# XbeeBed.net
KiCad netlist of a schematic drawn in Altium Designer
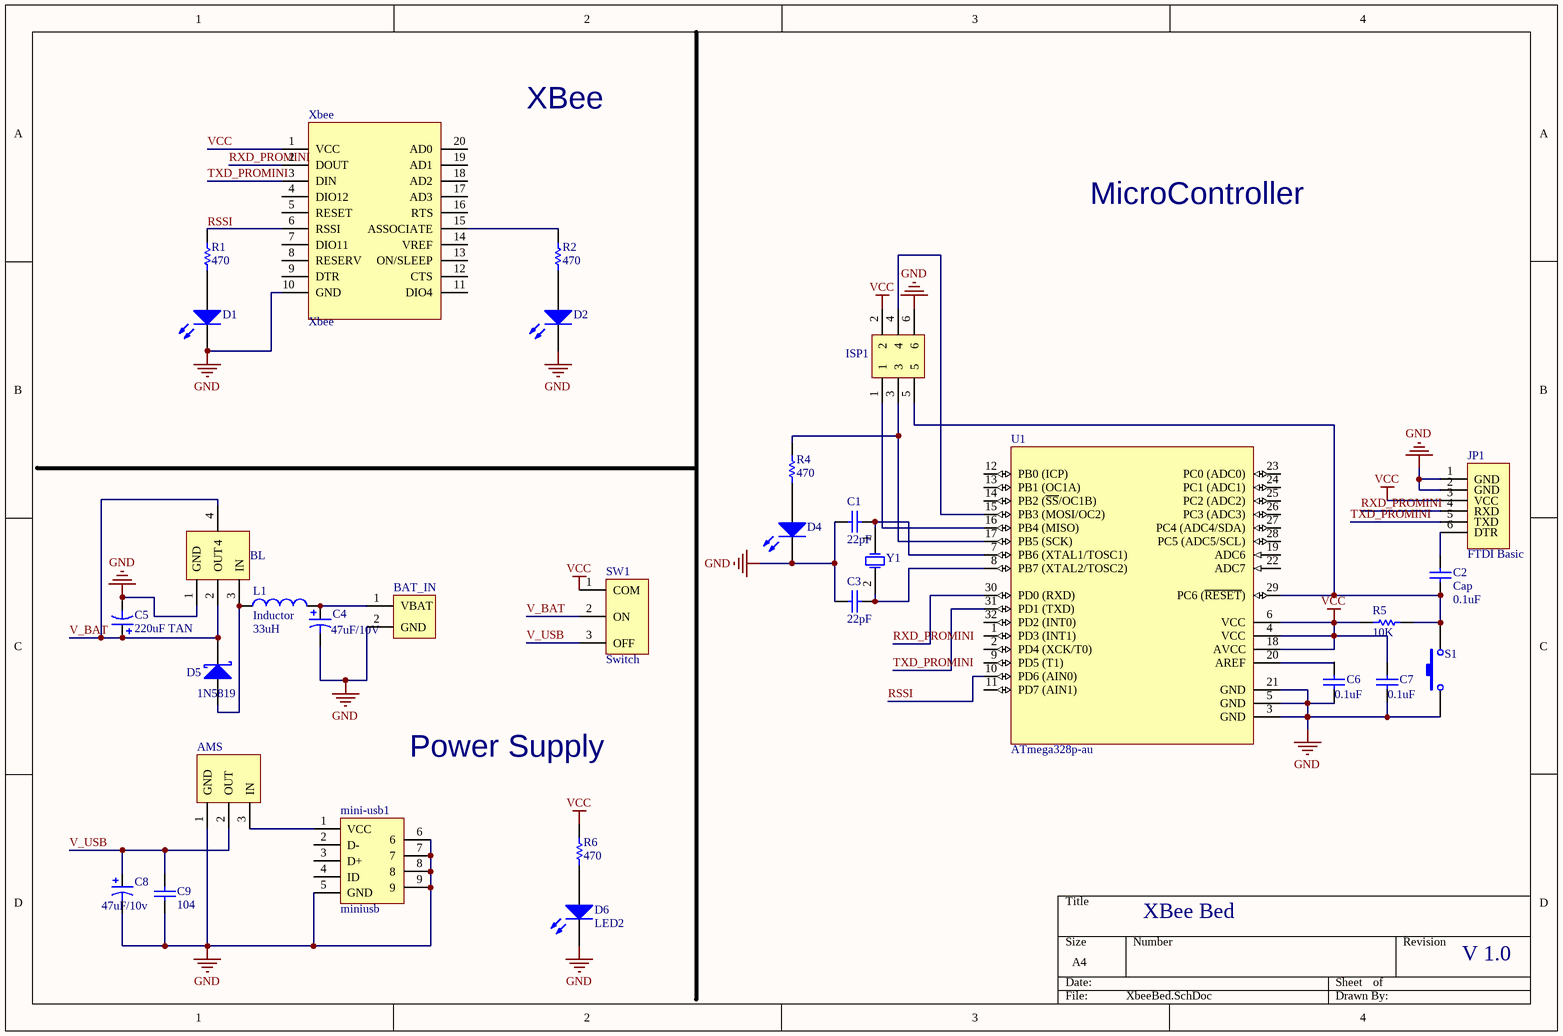
[diagram p0: XbeeBed.SchDoc]

(export (version "E")
  (design (tool "Eeschema 10.0.6"))
  (components
    (comp (ref "AMS")
      (value "AMS1117-3.3CD")
      (footprint "SOT223")
      (libsource (lib "*") (part "AMS1117-3.3CD"))
    )
    (comp (ref "BAT_IN") (value "BATTERY INPUT") (footprint "vbat_in") (libsource (lib "*") (part "BAT_IN")))
    (comp (ref "BL") (value "BL8530-331SM") (footprint "SOT89") (libsource (lib "*") (part "BL8530-331SM")))
    (comp (ref "C1")
      (value "22pF")
      (footprint "0805")
      (description "Capacitor")
      (fields (field (name "Comment") "Cap") (field (name "PUBLISHER") "Altium Limited"))
      (libsource (lib "Miscellaneous Devices") (part "Cap"))
    )
    (comp (ref "C2")
      (value "Cap")
      (footprint "0805")
      (description "Capacitor")
      (fields (field (name "ALTIUM_VALUE") "0.1uF") (field (name "PUBLISHER") "Altium Limited"))
      (libsource (lib "Miscellaneous Devices") (part "Cap"))
    )
    (comp (ref "C3")
      (value "22pF")
      (footprint "0805")
      (description "Capacitor")
      (fields (field (name "Comment") "Cap") (field (name "PUBLISHER") "Altium Limited"))
      (libsource (lib "Miscellaneous Devices") (part "Cap"))
    )
    (comp (ref "C4")
      (value "47uF/10V")
      (footprint "tan-c type")
      (description "Polarized Capacitor (Surface Mount)")
      (fields (field (name "Comment") "Cap Pol3") (field (name "PUBLISHER") "Altium Limited"))
      (libsource (lib "Miscellaneous Devices") (part "Cap Pol3"))
    )
    (comp (ref "C5")
      (value "220uF TAN")
      (footprint "tan-d type")
      (description "Polarized Capacitor (Surface Mount)")
      (fields (field (name "Comment") "Cap Pol3") (field (name "PUBLISHER") "Altium Limited"))
      (libsource (lib "") (part "Cap Pol3_1"))
    )
    (comp (ref "C6")
      (value "0.1uF")
      (footprint "0805")
      (description "Capacitor")
      (fields (field (name "Comment") "Cap") (field (name "PUBLISHER") "Altium Limited"))
      (libsource (lib "Miscellaneous Devices") (part "Cap"))
    )
    (comp (ref "C7")
      (value "0.1uF")
      (footprint "0805")
      (description "Capacitor")
      (fields (field (name "Comment") "Cap") (field (name "PUBLISHER") "Altium Limited"))
      (libsource (lib "Miscellaneous Devices") (part "Cap"))
    )
    (comp (ref "C8")
      (value "47uF/10v")
      (footprint "tan-c type")
      (description "Polarized Capacitor (Surface Mount)")
      (fields (field (name "Comment") "Cap Pol3") (field (name "PUBLISHER") "Altium Limited"))
      (libsource (lib "Miscellaneous Devices") (part "Cap Pol3"))
    )
    (comp (ref "C9")
      (value "104")
      (footprint "0805")
      (description "Capacitor")
      (fields (field (name "Comment") "Cap") (field (name "PUBLISHER") "Altium Limited"))
      (libsource (lib "Miscellaneous Devices") (part "Cap"))
    )
    (comp (ref "D1")
      (value "LED2")
      (footprint "0805")
      (description "Typical RED, GREEN, YELLOW, AMBER GaAs LED")
      (fields (field (name "PUBLISHER") "Altium Limited"))
      (libsource (lib "Miscellaneous Devices") (part "LED2"))
    )
    (comp (ref "D2")
      (value "LED2")
      (footprint "0805")
      (description "Typical RED, GREEN, YELLOW, AMBER GaAs LED")
      (fields (field (name "PUBLISHER") "Altium Limited"))
      (libsource (lib "Miscellaneous Devices") (part "LED2"))
    )
    (comp (ref "D4")
      (value "LED2")
      (footprint "0805")
      (description "Typical RED, GREEN, YELLOW, AMBER GaAs LED")
      (fields (field (name "PUBLISHER") "Altium Limited"))
      (libsource (lib "Miscellaneous Devices") (part "LED2"))
    )
    (comp (ref "D5")
      (value "1N5819")
      (footprint "1n5819")
      (description "Schottky Rectifier")
      (fields (field (name "PUBLISHER") "Altium Limited"))
      (libsource (lib "Miscellaneous Devices") (part "Diode 11DQ03"))
    )
    (comp (ref "D6")
      (value "LED2")
      (footprint "0805")
      (description "Typical RED, GREEN, YELLOW, AMBER GaAs LED")
      (fields (field (name "PUBLISHER") "Altium Limited"))
      (libsource (lib "Miscellaneous Devices") (part "LED2"))
    )
    (comp (ref "ISP1") (value "ISP INTERFACE") (footprint "icsp") (libsource (lib "*") (part "ISP")))
    (comp (ref "JP1") (value "FTDI Basic") (footprint "ftdi-basic") (libsource (lib "*") (part "FTDI Basic")))
    (comp (ref "L1")
      (value "Inductor")
      (footprint "33uh-cd43")
      (fields (field (name "ALTIUM_VALUE") "33uH") (field (name "PUBLISHER") "Altium Limited"))
      (libsource (lib "Miscellaneous Devices") (part "Inductor"))
    )
    (comp (ref "mini-usb1") (value "miniusb") (footprint "mini USB") (libsource (lib "*") (part "Mini-Usb")))
    (comp (ref "R1")
      (value "470")
      (footprint "0805")
      (description "Resistor")
      (fields (field (name "Comment") "Res1") (field (name "PUBLISHER") "Altium Limited"))
      (libsource (lib "Miscellaneous Devices") (part "Res1"))
    )
    (comp (ref "R2")
      (value "470")
      (footprint "0805")
      (description "Resistor")
      (fields (field (name "Comment") "Res1") (field (name "PUBLISHER") "Altium Limited"))
      (libsource (lib "Miscellaneous Devices") (part "Res1"))
    )
    (comp (ref "R4")
      (value "470")
      (footprint "0805")
      (description "Resistor")
      (fields (field (name "Comment") "Res1") (field (name "PUBLISHER") "Altium Limited"))
      (libsource (lib "Miscellaneous Devices") (part "Res1"))
    )
    (comp (ref "R5")
      (value "10K")
      (footprint "0805")
      (description "Resistor")
      (fields (field (name "Comment") "Res1") (field (name "PUBLISHER") "Altium Limited"))
      (libsource (lib "Miscellaneous Devices") (part "Res1"))
    )
    (comp (ref "R6")
      (value "470")
      (footprint "0805")
      (description "Resistor")
      (fields (field (name "Comment") "Res1") (field (name "PUBLISHER") "Altium Limited"))
      (libsource (lib "Miscellaneous Devices") (part "Res1"))
    )
    (comp (ref "S1")
      (value "SW-PB")
      (footprint "sw-pb")
      (description "Switch")
      (fields (field (name "PUBLISHER") "Altium Limited"))
      (libsource (lib "Miscellaneous Devices") (part "SW-PB"))
    )
    (comp (ref "SW1") (value "Switch") (footprint "switch") (libsource (lib "*") (part "SW")))
    (comp (ref "U1")
      (value "ATmega328p-au")
      (footprint "atmega328")
      (description "8-Bit AVR Microcontroller with 8K Bytes of In-System Programmable Flash Memory")
      (fields (field (name "PUBLISHER") "Altium Limited"))
      (libsource (lib "Atmel Microcontroller 8-Bit AVR") (part "ATmega8-16AC"))
    )
    (comp (ref "Xbee") (value "Xbee") (footprint "xbee") (libsource (lib "*") (part "Xbee")))
    (comp (ref "Y1")
      (value "XTAL")
      (footprint "8MHz")
      (description "Crystal Oscillator")
      (fields (field (name "PUBLISHER") "Altium Limited"))
      (libsource (lib "Miscellaneous Devices") (part "XTAL"))
    )
  )
  (nets
    (net (code "1") (name "/RSSI") (class "Default")
      (node (ref "R1") (pin "1") (pinfunction "1_1") (pintype "passive"))
      (node (ref "U1") (pin "10") (pinfunction "PD6_(AIN0)_10") (pintype "bidirectional"))
      (node (ref "Xbee") (pin "6") (pinfunction "RSSI_6") (pintype "passive"))
    )
    (net (code "2") (name "/RXD_PROMINI") (class "Default")
      (node (ref "JP1") (pin "4") (pinfunction "RXD_4") (pintype "passive"))
      (node (ref "U1") (pin "30") (pinfunction "PD0_(RXD)_30") (pintype "bidirectional"))
      (node (ref "Xbee") (pin "2") (pinfunction "DOUT_2") (pintype "passive"))
    )
    (net (code "3") (name "/TXD_PROMINI") (class "Default")
      (node (ref "JP1") (pin "5") (pinfunction "TXD_5") (pintype "passive"))
      (node (ref "U1") (pin "31") (pinfunction "PD1_(TXD)_31") (pintype "bidirectional"))
      (node (ref "Xbee") (pin "3") (pinfunction "DIN_3") (pintype "passive"))
    )
    (net (code "4") (name "/V_BAT") (class "Default")
      (node (ref "BL") (pin "2") (pinfunction "OUT_2") (pintype "passive"))
      (node (ref "BL") (pin "4") (pinfunction "4_4") (pintype "passive"))
      (node (ref "C5") (pin "1") (pinfunction "1_1") (pintype "passive"))
      (node (ref "D5") (pin "2") (pinfunction "K_2") (pintype "passive"))
      (node (ref "SW1") (pin "2") (pinfunction "ON_2") (pintype "passive"))
    )
    (net (code "5") (name "/V_USB") (class "Default")
      (node (ref "AMS") (pin "2") (pinfunction "OUT_2") (pintype "passive"))
      (node (ref "C8") (pin "1") (pinfunction "1_1") (pintype "passive"))
      (node (ref "C9") (pin "1") (pinfunction "1_1") (pintype "passive"))
      (node (ref "SW1") (pin "3") (pinfunction "OFF_3") (pintype "passive"))
    )
    (net (code "6") (name "GND") (class "Default")
      (node (ref "AMS") (pin "1") (pinfunction "GND_1") (pintype "passive"))
      (node (ref "BAT_IN") (pin "2") (pinfunction "GND_2") (pintype "passive"))
      (node (ref "BL") (pin "1") (pinfunction "GND_1") (pintype "passive"))
      (node (ref "C1") (pin "2") (pinfunction "2_2") (pintype "passive"))
      (node (ref "C3") (pin "2") (pinfunction "2_2") (pintype "passive"))
      (node (ref "C4") (pin "2") (pinfunction "2_2") (pintype "passive"))
      (node (ref "C5") (pin "2") (pinfunction "2_2") (pintype "passive"))
      (node (ref "C6") (pin "1") (pinfunction "1_1") (pintype "passive"))
      (node (ref "C7") (pin "1") (pinfunction "1_1") (pintype "passive"))
      (node (ref "C8") (pin "2") (pinfunction "2_2") (pintype "passive"))
      (node (ref "C9") (pin "2") (pinfunction "2_2") (pintype "passive"))
      (node (ref "D1") (pin "2") (pinfunction "K_2") (pintype "passive"))
      (node (ref "D2") (pin "2") (pinfunction "K_2") (pintype "passive"))
      (node (ref "D4") (pin "2") (pinfunction "K_2") (pintype "passive"))
      (node (ref "D6") (pin "2") (pinfunction "K_2") (pintype "passive"))
      (node (ref "ISP1") (pin "6") (pinfunction "6_6") (pintype "passive"))
      (node (ref "JP1") (pin "1") (pinfunction "GND_1") (pintype "passive"))
      (node (ref "JP1") (pin "2") (pinfunction "GND_2") (pintype "passive"))
      (node (ref "S1") (pin "1") (pinfunction "1_1") (pintype "passive"))
      (node (ref "U1") (pin "21") (pinfunction "GND_21") (pintype "power_in"))
      (node (ref "U1") (pin "3") (pinfunction "GND_3") (pintype "power_in"))
      (node (ref "U1") (pin "5") (pinfunction "GND_5") (pintype "power_in"))
      (node (ref "Xbee") (pin "10") (pinfunction "GND_10") (pintype "passive"))
      (node (ref "mini-usb1") (pin "5") (pinfunction "GND_5") (pintype "passive"))
      (node (ref "mini-usb1") (pin "6") (pinfunction "6_6") (pintype "passive"))
      (node (ref "mini-usb1") (pin "7") (pinfunction "7_7") (pintype "passive"))
      (node (ref "mini-usb1") (pin "8") (pinfunction "8_8") (pintype "passive"))
      (node (ref "mini-usb1") (pin "9") (pinfunction "9_9") (pintype "passive"))
    )
    (net (code "7") (name "Net-(AMS-IN)") (class "Default")
      (node (ref "AMS") (pin "3") (pinfunction "IN_3") (pintype "passive"))
      (node (ref "mini-usb1") (pin "1") (pinfunction "VCC_1") (pintype "passive"))
    )
    (net (code "8") (name "Net-(BAT_IN-VBAT)") (class "Default")
      (node (ref "BAT_IN") (pin "1") (pinfunction "VBAT_1") (pintype "passive"))
      (node (ref "C4") (pin "1") (pinfunction "1_1") (pintype "passive"))
      (node (ref "L1") (pin "2") (pinfunction "2_2") (pintype "passive"))
    )
    (net (code "9") (name "Net-(BL-IN)") (class "Default")
      (node (ref "BL") (pin "3") (pinfunction "IN_3") (pintype "passive"))
      (node (ref "D5") (pin "1") (pinfunction "A_1") (pintype "passive"))
      (node (ref "L1") (pin "1") (pinfunction "1_1") (pintype "passive"))
    )
    (net (code "10") (name "Net-(D1-A)") (class "Default")
      (node (ref "D1") (pin "1") (pinfunction "A_1") (pintype "passive"))
      (node (ref "R1") (pin "2") (pinfunction "2_2") (pintype "passive"))
    )
    (net (code "11") (name "Net-(D2-A)") (class "Default")
      (node (ref "D2") (pin "1") (pinfunction "A_1") (pintype "passive"))
      (node (ref "R2") (pin "2") (pinfunction "2_2") (pintype "passive"))
    )
    (net (code "12") (name "Net-(D4-A)") (class "Default")
      (node (ref "D4") (pin "1") (pinfunction "A_1") (pintype "passive"))
      (node (ref "R4") (pin "2") (pinfunction "2_2") (pintype "passive"))
    )
    (net (code "13") (name "Net-(D6-A)") (class "Default")
      (node (ref "D6") (pin "1") (pinfunction "A_1") (pintype "passive"))
      (node (ref "R6") (pin "2") (pinfunction "2_2") (pintype "passive"))
    )
    (net (code "14") (name "Net-(JP1-DTR)") (class "Default")
      (node (ref "C2") (pin "2") (pinfunction "2_2") (pintype "passive"))
      (node (ref "JP1") (pin "6") (pinfunction "DTR_6") (pintype "passive"))
    )
    (net (code "15") (name "Net-(U1-AREF)") (class "Default")
      (node (ref "C6") (pin "2") (pinfunction "2_2") (pintype "passive"))
      (node (ref "U1") (pin "20") (pinfunction "AREF_20") (pintype "passive"))
    )
    (net (code "16") (name "Net-(U1-PB3_(MOSI{slash}OC2))") (class "Default")
      (node (ref "ISP1") (pin "4") (pinfunction "4_4") (pintype "passive"))
      (node (ref "U1") (pin "15") (pinfunction "PB3_(MOSI/OC2)_15") (pintype "bidirectional"))
    )
    (net (code "17") (name "Net-(U1-PB4_(MISO))") (class "Default")
      (node (ref "ISP1") (pin "1") (pinfunction "1_1") (pintype "passive"))
      (node (ref "U1") (pin "16") (pinfunction "PB4_(MISO)_16") (pintype "bidirectional"))
    )
    (net (code "18") (name "Net-(U1-PB5_(SCK))") (class "Default")
      (node (ref "ISP1") (pin "3") (pinfunction "3_3") (pintype "passive"))
      (node (ref "R4") (pin "1") (pinfunction "1_1") (pintype "passive"))
      (node (ref "U1") (pin "17") (pinfunction "PB5_(SCK)_17") (pintype "bidirectional"))
    )
    (net (code "19") (name "Net-(U1-PB6_(XTAL1{slash}TOSC1))") (class "Default")
      (node (ref "C1") (pin "1") (pinfunction "1_1") (pintype "passive"))
      (node (ref "U1") (pin "7") (pinfunction "PB6_(XTAL1/TOSC1)_7") (pintype "bidirectional"))
      (node (ref "Y1") (pin "1") (pinfunction "OSC1_1") (pintype "passive"))
    )
    (net (code "20") (name "Net-(U1-PB7_(XTAL2{slash}TOSC2))") (class "Default")
      (node (ref "C3") (pin "1") (pinfunction "1_1") (pintype "passive"))
      (node (ref "U1") (pin "8") (pinfunction "PB7_(XTAL2/TOSC2)_8") (pintype "bidirectional"))
      (node (ref "Y1") (pin "2") (pinfunction "OSC2_2") (pintype "passive"))
    )
    (net (code "21") (name "Net-(U1-PC6_(~{RESET}))") (class "Default")
      (node (ref "C2") (pin "1") (pinfunction "1_1") (pintype "passive"))
      (node (ref "ISP1") (pin "5") (pinfunction "5_5") (pintype "passive"))
      (node (ref "R5") (pin "1") (pinfunction "1_1") (pintype "passive"))
      (node (ref "S1") (pin "2") (pinfunction "2_2") (pintype "passive"))
      (node (ref "U1") (pin "29") (pinfunction "PC6_(~{RESET})_29") (pintype "bidirectional"))
    )
    (net (code "22") (name "Net-(Xbee-ASSOCIATE)") (class "Default")
      (node (ref "R2") (pin "1") (pinfunction "1_1") (pintype "passive"))
      (node (ref "Xbee") (pin "15") (pinfunction "ASSOCIATE_15") (pintype "passive"))
    )
    (net (code "23") (name "VCC") (class "Default")
      (node (ref "C7") (pin "2") (pinfunction "2_2") (pintype "passive"))
      (node (ref "ISP1") (pin "2") (pinfunction "2_2") (pintype "passive"))
      (node (ref "JP1") (pin "3") (pinfunction "VCC_3") (pintype "passive"))
      (node (ref "R5") (pin "2") (pinfunction "2_2") (pintype "passive"))
      (node (ref "R6") (pin "1") (pinfunction "1_1") (pintype "passive"))
      (node (ref "SW1") (pin "1") (pinfunction "COM_1") (pintype "passive"))
      (node (ref "U1") (pin "18") (pinfunction "AVCC_18") (pintype "power_in"))
      (node (ref "U1") (pin "4") (pinfunction "VCC_4") (pintype "power_in"))
      (node (ref "U1") (pin "6") (pinfunction "VCC_6") (pintype "power_in"))
      (node (ref "Xbee") (pin "1") (pinfunction "VCC_1") (pintype "passive"))
    )
    (net (code "24") (name "unconnected-(U1-ADC6-Pad19)") (class "Default")
      (node (ref "U1") (pin "19") (pinfunction "ADC6_19") (pintype "input"))
    )
    (net (code "25") (name "unconnected-(U1-ADC7-Pad22)") (class "Default")
      (node (ref "U1") (pin "22") (pinfunction "ADC7_22") (pintype "input"))
    )
    (net (code "26") (name "unconnected-(U1-PB0_(ICP)-Pad12)") (class "Default")
      (node (ref "U1") (pin "12") (pinfunction "PB0_(ICP)_12") (pintype "bidirectional"))
    )
    (net (code "27") (name "unconnected-(U1-PB1_(OC1A)-Pad13)") (class "Default")
      (node (ref "U1") (pin "13") (pinfunction "PB1_(OC1A)_13") (pintype "bidirectional"))
    )
    (net (code "28") (name "unconnected-(U1-PB2_(~{SS}{slash}OC1B)-Pad14)") (class "Default")
      (node (ref "U1") (pin "14") (pinfunction "PB2_(~{SS}/OC1B)_14") (pintype "bidirectional"))
    )
    (net (code "29") (name "unconnected-(U1-PC0_(ADC0)-Pad23)") (class "Default")
      (node (ref "U1") (pin "23") (pinfunction "PC0_(ADC0)_23") (pintype "bidirectional"))
    )
    (net (code "30") (name "unconnected-(U1-PC1_(ADC1)-Pad24)") (class "Default")
      (node (ref "U1") (pin "24") (pinfunction "PC1_(ADC1)_24") (pintype "bidirectional"))
    )
    (net (code "31") (name "unconnected-(U1-PC2_(ADC2)-Pad25)") (class "Default")
      (node (ref "U1") (pin "25") (pinfunction "PC2_(ADC2)_25") (pintype "bidirectional"))
    )
    (net (code "32") (name "unconnected-(U1-PC3_(ADC3)-Pad26)") (class "Default")
      (node (ref "U1") (pin "26") (pinfunction "PC3_(ADC3)_26") (pintype "bidirectional"))
    )
    (net (code "33") (name "unconnected-(U1-PC4_(ADC4{slash}SDA)-Pad27)") (class "Default")
      (node (ref "U1") (pin "27") (pinfunction "PC4_(ADC4/SDA)_27") (pintype "bidirectional"))
    )
    (net (code "34") (name "unconnected-(U1-PC5_(ADC5{slash}SCL)-Pad28)") (class "Default")
      (node (ref "U1") (pin "28") (pinfunction "PC5_(ADC5/SCL)_28") (pintype "bidirectional"))
    )
    (net (code "35") (name "unconnected-(U1-PD2_(INT0)-Pad32)") (class "Default")
      (node (ref "U1") (pin "32") (pinfunction "PD2_(INT0)_32") (pintype "bidirectional"))
    )
    (net (code "36") (name "unconnected-(U1-PD3_(INT1)-Pad1)") (class "Default")
      (node (ref "U1") (pin "1") (pinfunction "PD3_(INT1)_1") (pintype "bidirectional"))
    )
    (net (code "37") (name "unconnected-(U1-PD4_(XCK{slash}T0)-Pad2)") (class "Default")
      (node (ref "U1") (pin "2") (pinfunction "PD4_(XCK/T0)_2") (pintype "bidirectional"))
    )
    (net (code "38") (name "unconnected-(U1-PD5_(T1)-Pad9)") (class "Default")
      (node (ref "U1") (pin "9") (pinfunction "PD5_(T1)_9") (pintype "bidirectional"))
    )
    (net (code "39") (name "unconnected-(U1-PD7_(AIN1)-Pad11)") (class "Default")
      (node (ref "U1") (pin "11") (pinfunction "PD7_(AIN1)_11") (pintype "bidirectional"))
    )
    (net (code "40") (name "unconnected-(Xbee-AD0-Pad20)") (class "Default")
      (node (ref "Xbee") (pin "20") (pinfunction "AD0_20") (pintype "passive"))
    )
    (net (code "41") (name "unconnected-(Xbee-AD1-Pad19)") (class "Default")
      (node (ref "Xbee") (pin "19") (pinfunction "AD1_19") (pintype "passive"))
    )
    (net (code "42") (name "unconnected-(Xbee-AD2-Pad18)") (class "Default")
      (node (ref "Xbee") (pin "18") (pinfunction "AD2_18") (pintype "passive"))
    )
    (net (code "43") (name "unconnected-(Xbee-AD3-Pad17)") (class "Default")
      (node (ref "Xbee") (pin "17") (pinfunction "AD3_17") (pintype "passive"))
    )
    (net (code "44") (name "unconnected-(Xbee-CTS-Pad12)") (class "Default")
      (node (ref "Xbee") (pin "12") (pinfunction "CTS_12") (pintype "passive"))
    )
    (net (code "45") (name "unconnected-(Xbee-DIO4-Pad11)") (class "Default")
      (node (ref "Xbee") (pin "11") (pinfunction "DIO4_11") (pintype "passive"))
    )
    (net (code "46") (name "unconnected-(Xbee-DIO11-Pad7)") (class "Default")
      (node (ref "Xbee") (pin "7") (pinfunction "DIO11_7") (pintype "passive"))
    )
    (net (code "47") (name "unconnected-(Xbee-DIO12-Pad4)") (class "Default")
      (node (ref "Xbee") (pin "4") (pinfunction "DIO12_4") (pintype "passive"))
    )
    (net (code "48") (name "unconnected-(Xbee-DTR-Pad9)") (class "Default")
      (node (ref "Xbee") (pin "9") (pinfunction "DTR_9") (pintype "passive"))
    )
    (net (code "49") (name "unconnected-(Xbee-ON{slash}SLEEP-Pad13)") (class "Default")
      (node (ref "Xbee") (pin "13") (pinfunction "ON/SLEEP_13") (pintype "passive"))
    )
    (net (code "50") (name "unconnected-(Xbee-RESERV-Pad8)") (class "Default")
      (node (ref "Xbee") (pin "8") (pinfunction "RESERV_8") (pintype "passive"))
    )
    (net (code "51") (name "unconnected-(Xbee-RESET-Pad5)") (class "Default")
      (node (ref "Xbee") (pin "5") (pinfunction "RESET_5") (pintype "passive"))
    )
    (net (code "52") (name "unconnected-(Xbee-RTS-Pad16)") (class "Default")
      (node (ref "Xbee") (pin "16") (pinfunction "RTS_16") (pintype "passive"))
    )
    (net (code "53") (name "unconnected-(Xbee-VREF-Pad14)") (class "Default")
      (node (ref "Xbee") (pin "14") (pinfunction "VREF_14") (pintype "passive"))
    )
    (net (code "54") (name "unconnected-(mini-usb1-D+-Pad3)") (class "Default")
      (node (ref "mini-usb1") (pin "3") (pinfunction "D+_3") (pintype "passive"))
    )
    (net (code "55") (name "unconnected-(mini-usb1-D--Pad2)") (class "Default")
      (node (ref "mini-usb1") (pin "2") (pinfunction "D-_2") (pintype "passive"))
    )
    (net (code "56") (name "unconnected-(mini-usb1-ID-Pad4)") (class "Default")
      (node (ref "mini-usb1") (pin "4") (pinfunction "ID_4") (pintype "passive"))
    )
  )
)
